# main_board.net
KiCad netlist of a schematic drawn in EAGLE
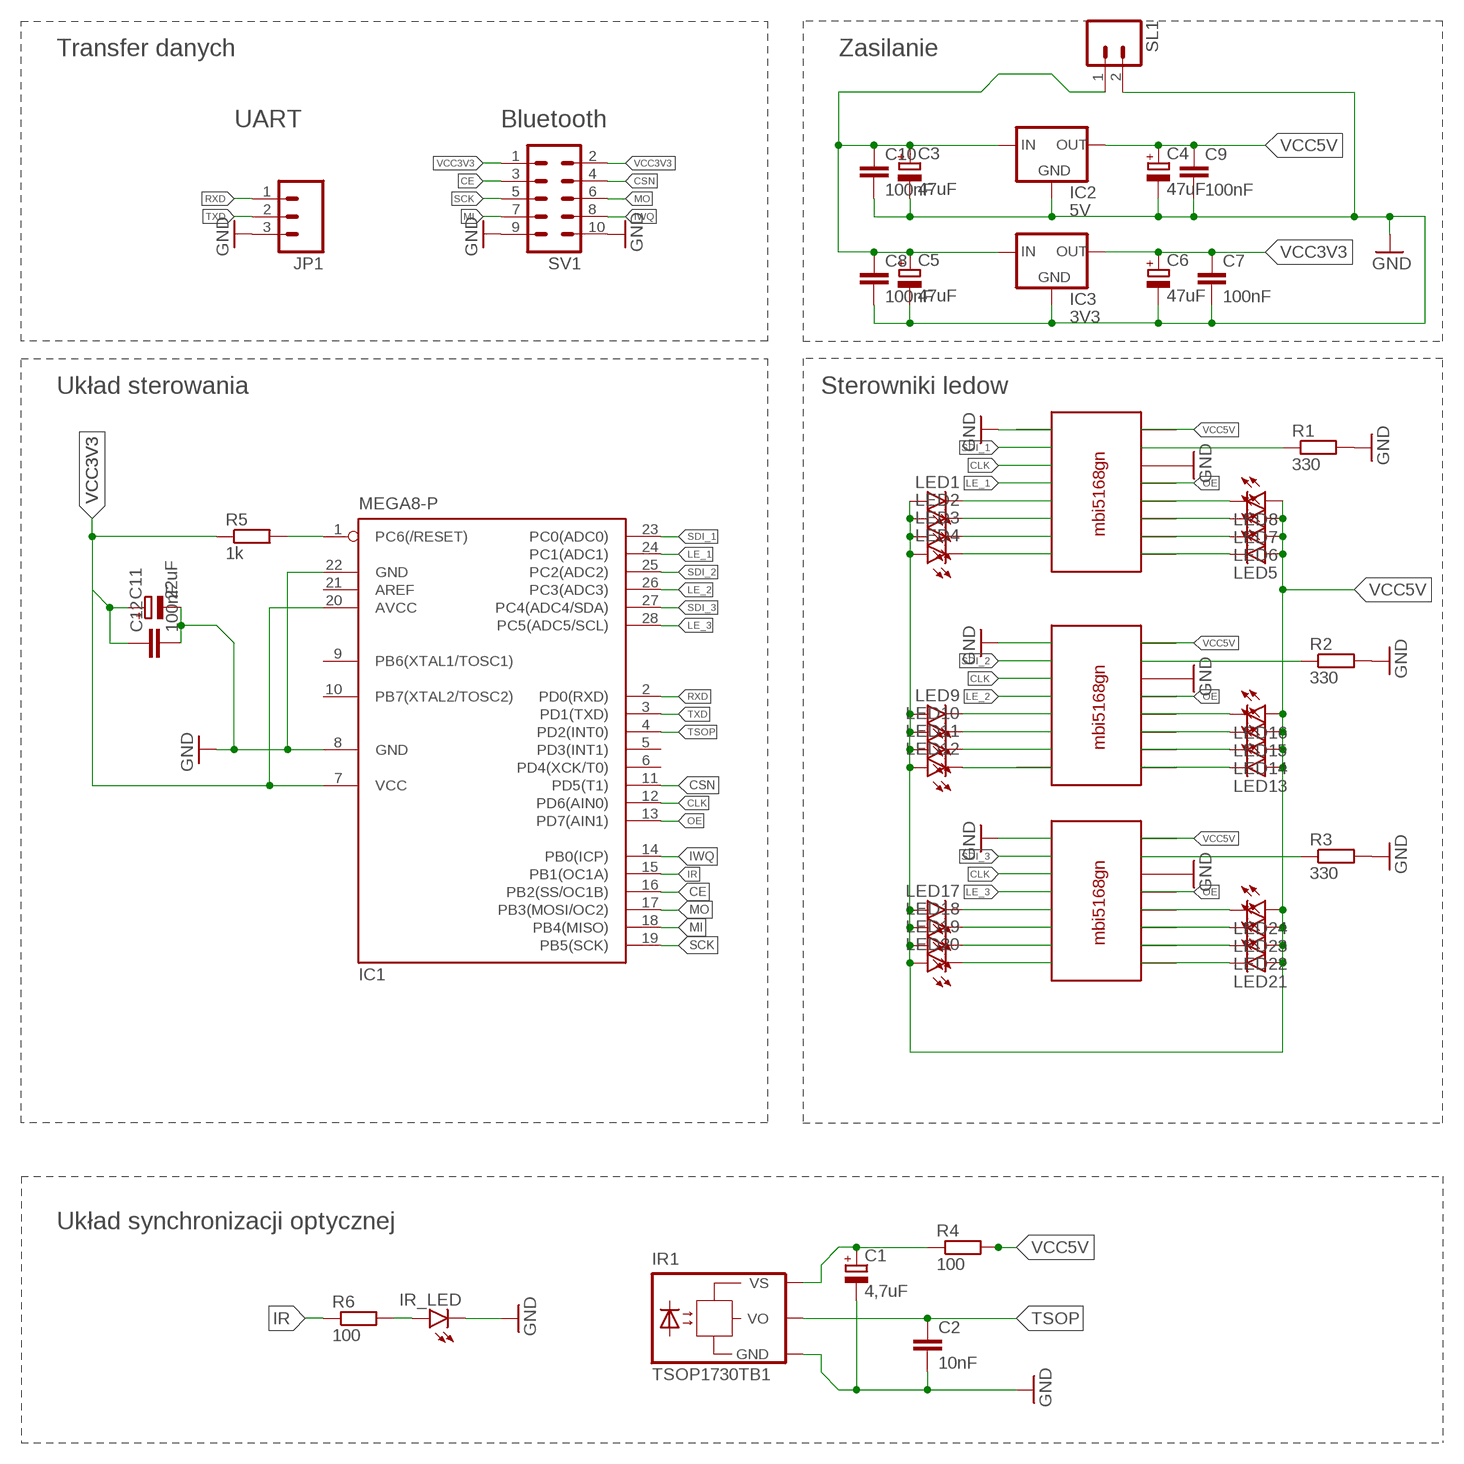
[diagram p0: schematic, sheet 1]

(export (version "E")
  (design (tool "Eeschema 10.0.6"))
  (components
    (comp (ref "C1")
      (value "4,7uF")
      (footprint "eagle-import:B45181A")
      (libsource (lib "eagle-import") (part "CPOL-EUB45181A"))
    )
    (comp (ref "C2")
      (value "10nF")
      (footprint "eagle-import:C025-040X050")
      (libsource (lib "eagle-import") (part "C-EU025-040X050"))
    )
    (comp (ref "C3")
      (value "47uF")
      (footprint "eagle-import:B45181A")
      (libsource (lib "eagle-import") (part "CPOL-EUB45181A"))
    )
    (comp (ref "C4")
      (value "47uF")
      (footprint "eagle-import:B45181A")
      (libsource (lib "eagle-import") (part "CPOL-EUB45181A"))
    )
    (comp (ref "C5")
      (value "47uF")
      (footprint "eagle-import:B45181A")
      (libsource (lib "eagle-import") (part "CPOL-EUB45181A"))
    )
    (comp (ref "C6")
      (value "47uF")
      (footprint "eagle-import:B45181A")
      (libsource (lib "eagle-import") (part "CPOL-EUB45181A"))
    )
    (comp (ref "C7")
      (value "100nF")
      (footprint "eagle-import:C0805")
      (libsource (lib "eagle-import") (part "C-EUC0805"))
    )
    (comp (ref "C8")
      (value "100nF")
      (footprint "eagle-import:C0805")
      (libsource (lib "eagle-import") (part "C-EUC0805"))
    )
    (comp (ref "C9")
      (value "100nF")
      (footprint "eagle-import:C0805")
      (libsource (lib "eagle-import") (part "C-EUC0805"))
    )
    (comp (ref "C10")
      (value "100nF")
      (footprint "eagle-import:C0805")
      (libsource (lib "eagle-import") (part "C-EUC0805"))
    )
    (comp (ref "C11")
      (value "22uF")
      (footprint "eagle-import:B45181A")
      (libsource (lib "eagle-import") (part "CPOL-EUB45181A"))
    )
    (comp (ref "C12")
      (value "100nF")
      (footprint "eagle-import:C025-040X050")
      (libsource (lib "eagle-import") (part "C-EU025-040X050"))
    )
    (comp (ref "IC1")
      (value "MEGA8-P")
      (footprint "eagle-import:DIL28-3")
      (libsource (lib "eagle-import") (part "MEGA8-P"))
    )
    (comp (ref "IC2")
      (value "5V")
      (footprint "eagle-import:TO-220-ALT")
      (libsource (lib "eagle-import") (part "V_REG_78XX-TO-220"))
    )
    (comp (ref "IC3")
      (value "3V3")
      (footprint "eagle-import:TO-220-ALT")
      (libsource (lib "eagle-import") (part "V_REG_78XX-TO-220"))
    )
    (comp (ref "IR1")
      (value "TSOP1730TB1")
      (footprint "eagle-import:TSOP17_TB1")
      (libsource (lib "eagle-import") (part "TSOP17TB130"))
    )
    (comp (ref "IR_LED")
      (value "LED5MM")
      (footprint "eagle-import:LED5MM")
      (libsource (lib "eagle-import") (part "LED5MM"))
    )
    (comp (ref "JP1")
      (value "M03PTH")
      (footprint "eagle-import:1X03")
      (libsource (lib "eagle-import") (part "M03PTH"))
    )
    (comp (ref "LED1")
      (value "LED3MM")
      (footprint "eagle-import:LED3MM")
      (libsource (lib "eagle-import") (part "LED3MM"))
    )
    (comp (ref "LED2")
      (value "LED3MM")
      (footprint "eagle-import:LED3MM")
      (libsource (lib "eagle-import") (part "LED3MM"))
    )
    (comp (ref "LED3")
      (value "LED3MM")
      (footprint "eagle-import:LED3MM")
      (libsource (lib "eagle-import") (part "LED3MM"))
    )
    (comp (ref "LED4")
      (value "LED3MM")
      (footprint "eagle-import:LED3MM")
      (libsource (lib "eagle-import") (part "LED3MM"))
    )
    (comp (ref "LED5")
      (value "LED3MM")
      (footprint "eagle-import:LED3MM")
      (libsource (lib "eagle-import") (part "LED3MM"))
    )
    (comp (ref "LED6")
      (value "LED3MM")
      (footprint "eagle-import:LED3MM")
      (libsource (lib "eagle-import") (part "LED3MM"))
    )
    (comp (ref "LED7")
      (value "LED3MM")
      (footprint "eagle-import:LED3MM")
      (libsource (lib "eagle-import") (part "LED3MM"))
    )
    (comp (ref "LED8")
      (value "LED3MM")
      (footprint "eagle-import:LED3MM")
      (libsource (lib "eagle-import") (part "LED3MM"))
    )
    (comp (ref "LED9")
      (value "LED3MM")
      (footprint "eagle-import:LED3MM")
      (libsource (lib "eagle-import") (part "LED3MM"))
    )
    (comp (ref "LED10")
      (value "LED3MM")
      (footprint "eagle-import:LED3MM")
      (libsource (lib "eagle-import") (part "LED3MM"))
    )
    (comp (ref "LED11")
      (value "LED3MM")
      (footprint "eagle-import:LED3MM")
      (libsource (lib "eagle-import") (part "LED3MM"))
    )
    (comp (ref "LED12")
      (value "LED3MM")
      (footprint "eagle-import:LED3MM")
      (libsource (lib "eagle-import") (part "LED3MM"))
    )
    (comp (ref "LED13")
      (value "LED3MM")
      (footprint "eagle-import:LED3MM")
      (libsource (lib "eagle-import") (part "LED3MM"))
    )
    (comp (ref "LED14")
      (value "LED3MM")
      (footprint "eagle-import:LED3MM")
      (libsource (lib "eagle-import") (part "LED3MM"))
    )
    (comp (ref "LED15")
      (value "LED3MM")
      (footprint "eagle-import:LED3MM")
      (libsource (lib "eagle-import") (part "LED3MM"))
    )
    (comp (ref "LED16")
      (value "LED3MM")
      (footprint "eagle-import:LED3MM")
      (libsource (lib "eagle-import") (part "LED3MM"))
    )
    (comp (ref "LED17")
      (value "LED3MM")
      (footprint "eagle-import:LED3MM")
      (libsource (lib "eagle-import") (part "LED3MM"))
    )
    (comp (ref "LED18")
      (value "LED3MM")
      (footprint "eagle-import:LED3MM")
      (libsource (lib "eagle-import") (part "LED3MM"))
    )
    (comp (ref "LED19")
      (value "LED3MM")
      (footprint "eagle-import:LED3MM")
      (libsource (lib "eagle-import") (part "LED3MM"))
    )
    (comp (ref "LED20")
      (value "LED3MM")
      (footprint "eagle-import:LED3MM")
      (libsource (lib "eagle-import") (part "LED3MM"))
    )
    (comp (ref "LED21")
      (value "LED3MM")
      (footprint "eagle-import:LED3MM")
      (libsource (lib "eagle-import") (part "LED3MM"))
    )
    (comp (ref "LED22")
      (value "LED3MM")
      (footprint "eagle-import:LED3MM")
      (libsource (lib "eagle-import") (part "LED3MM"))
    )
    (comp (ref "LED23")
      (value "LED3MM")
      (footprint "eagle-import:LED3MM")
      (libsource (lib "eagle-import") (part "LED3MM"))
    )
    (comp (ref "LED24")
      (value "LED3MM")
      (footprint "eagle-import:LED3MM")
      (libsource (lib "eagle-import") (part "LED3MM"))
    )
    (comp (ref "R1")
      (value "330")
      (footprint "eagle-import:M0805")
      (libsource (lib "eagle-import") (part "R-EU_M0805"))
    )
    (comp (ref "R2")
      (value "330")
      (footprint "eagle-import:M0805")
      (libsource (lib "eagle-import") (part "R-EU_M0805"))
    )
    (comp (ref "R3")
      (value "330")
      (footprint "eagle-import:M0805")
      (libsource (lib "eagle-import") (part "R-EU_M0805"))
    )
    (comp (ref "R4")
      (value "100")
      (footprint "eagle-import:M0805")
      (libsource (lib "eagle-import") (part "R-EU_M0805"))
    )
    (comp (ref "R5")
      (value "1k")
      (footprint "eagle-import:M0805")
      (libsource (lib "eagle-import") (part "R-EU_M0805"))
    )
    (comp (ref "R6")
      (value "100")
      (footprint "eagle-import:M0805")
      (libsource (lib "eagle-import") (part "R-EU_M0805"))
    )
    (comp (ref "SL1")
      (value "M02")
      (footprint "eagle-import:02P")
      (libsource (lib "eagle-import") (part "M02"))
    )
    (comp (ref "SV1")
      (value "MA05-2")
      (footprint "eagle-import:MA05-2")
      (libsource (lib "eagle-import") (part "MA05-2"))
    )
    (comp (ref "U$1")
      (value "MBI5168GN")
      (footprint "eagle-import:DIL16")
      (libsource (lib "eagle-import") (part "MBI5168GN"))
    )
    (comp (ref "U$2")
      (value "MBI5168GN")
      (footprint "eagle-import:DIL16")
      (libsource (lib "eagle-import") (part "MBI5168GN"))
    )
    (comp (ref "U$3")
      (value "MBI5168GN")
      (footprint "eagle-import:DIL16")
      (libsource (lib "eagle-import") (part "MBI5168GN"))
    )
  )
  (nets
    (net (code "1") (name "CE") (class "Default")
      (node (ref "IC1") (pin "16") (pinfunction "PB2(SS/OC1B)_16") (pintype "bidirectional"))
      (node (ref "SV1") (pin "3") (pinfunction "3_3") (pintype "passive"))
    )
    (net (code "2") (name "CLK") (class "Default")
      (node (ref "IC1") (pin "12") (pinfunction "PD6(AIN0)_12") (pintype "bidirectional"))
      (node (ref "U$1") (pin "CLK") (pinfunction "CLK_CLK") (pintype "output"))
      (node (ref "U$2") (pin "CLK") (pinfunction "CLK_CLK") (pintype "output"))
      (node (ref "U$3") (pin "CLK") (pinfunction "CLK_CLK") (pintype "output"))
    )
    (net (code "3") (name "CSN") (class "Default")
      (node (ref "IC1") (pin "11") (pinfunction "PD5(T1)_11") (pintype "bidirectional"))
      (node (ref "SV1") (pin "4") (pinfunction "4_4") (pintype "passive"))
    )
    (net (code "4") (name "GND") (class "Default")
      (node (ref "C1") (pin "-") (pinfunction "-_-") (pintype "passive"))
      (node (ref "C10") (pin "2") (pinfunction "2_2") (pintype "passive"))
      (node (ref "C11") (pin "-") (pinfunction "-_-") (pintype "passive"))
      (node (ref "C12") (pin "2") (pinfunction "2_2") (pintype "passive"))
      (node (ref "C2") (pin "2") (pinfunction "2_2") (pintype "passive"))
      (node (ref "C3") (pin "-") (pinfunction "-_-") (pintype "passive"))
      (node (ref "C4") (pin "-") (pinfunction "-_-") (pintype "passive"))
      (node (ref "C5") (pin "-") (pinfunction "-_-") (pintype "passive"))
      (node (ref "C6") (pin "-") (pinfunction "-_-") (pintype "passive"))
      (node (ref "C7") (pin "2") (pinfunction "2_2") (pintype "passive"))
      (node (ref "C8") (pin "2") (pinfunction "2_2") (pintype "passive"))
      (node (ref "C9") (pin "2") (pinfunction "2_2") (pintype "passive"))
      (node (ref "IC1") (pin "22") (pinfunction "GND_22") (pintype "power_in"))
      (node (ref "IC1") (pin "8") (pinfunction "GND_8") (pintype "power_in"))
      (node (ref "IC2") (pin "GND") (pinfunction "GND_GND") (pintype "input"))
      (node (ref "IC3") (pin "GND") (pinfunction "GND_GND") (pintype "input"))
      (node (ref "IR1") (pin "GND") (pinfunction "GND_GND") (pintype "power_in"))
      (node (ref "IR_LED") (pin "K") (pinfunction "C_K") (pintype "passive"))
      (node (ref "JP1") (pin "3") (pinfunction "3_3") (pintype "passive"))
      (node (ref "R1") (pin "2") (pinfunction "2_2") (pintype "passive"))
      (node (ref "R2") (pin "2") (pinfunction "2_2") (pintype "passive"))
      (node (ref "R3") (pin "2") (pinfunction "2_2") (pintype "passive"))
      (node (ref "SL1") (pin "2") (pinfunction "2_2") (pintype "passive"))
      (node (ref "SV1") (pin "10") (pinfunction "10_10") (pintype "passive"))
      (node (ref "SV1") (pin "9") (pinfunction "9_9") (pintype "passive"))
      (node (ref "U$1") (pin "GND") (pinfunction "GND_GND") (pintype "output"))
      (node (ref "U$2") (pin "GND") (pinfunction "GND_GND") (pintype "output"))
      (node (ref "U$3") (pin "GND") (pinfunction "GND_GND") (pintype "output"))
    )
    (net (code "5") (name "IR") (class "Default")
      (node (ref "IC1") (pin "15") (pinfunction "PB1(OC1A)_15") (pintype "bidirectional"))
      (node (ref "R6") (pin "1") (pinfunction "1_1") (pintype "passive"))
    )
    (net (code "6") (name "IWQ") (class "Default")
      (node (ref "IC1") (pin "14") (pinfunction "PB0(ICP)_14") (pintype "bidirectional"))
      (node (ref "SV1") (pin "8") (pinfunction "8_8") (pintype "passive"))
    )
    (net (code "7") (name "LE_1") (class "Default")
      (node (ref "IC1") (pin "24") (pinfunction "PC1(ADC1)_24") (pintype "bidirectional"))
      (node (ref "U$1") (pin "LE") (pinfunction "LE_LE") (pintype "output"))
    )
    (net (code "8") (name "LE_2") (class "Default")
      (node (ref "IC1") (pin "26") (pinfunction "PC3(ADC3)_26") (pintype "bidirectional"))
      (node (ref "U$2") (pin "LE") (pinfunction "LE_LE") (pintype "output"))
    )
    (net (code "9") (name "LE_3") (class "Default")
      (node (ref "IC1") (pin "28") (pinfunction "PC5(ADC5/SCL)_28") (pintype "bidirectional"))
      (node (ref "U$3") (pin "LE") (pinfunction "LE_LE") (pintype "output"))
    )
    (net (code "10") (name "MI") (class "Default")
      (node (ref "IC1") (pin "18") (pinfunction "PB4(MISO)_18") (pintype "bidirectional"))
      (node (ref "SV1") (pin "7") (pinfunction "7_7") (pintype "passive"))
    )
    (net (code "11") (name "MO") (class "Default")
      (node (ref "IC1") (pin "17") (pinfunction "PB3(MOSI/OC2)_17") (pintype "bidirectional"))
      (node (ref "SV1") (pin "6") (pinfunction "6_6") (pintype "passive"))
    )
    (net (code "12") (name "Net-(C1-Pad+)") (class "Default")
      (node (ref "C1") (pin "+") (pinfunction "+_+") (pintype "passive"))
      (node (ref "IR1") (pin "VS") (pinfunction "VS_VS") (pintype "power_in"))
      (node (ref "R4") (pin "1") (pinfunction "1_1") (pintype "passive"))
    )
    (net (code "13") (name "Net-(C10-Pad1)") (class "Default")
      (node (ref "C10") (pin "1") (pinfunction "1_1") (pintype "passive"))
      (node (ref "C3") (pin "+") (pinfunction "+_+") (pintype "passive"))
      (node (ref "C5") (pin "+") (pinfunction "+_+") (pintype "passive"))
      (node (ref "C8") (pin "1") (pinfunction "1_1") (pintype "passive"))
      (node (ref "IC2") (pin "IN") (pinfunction "IN_IN") (pintype "input"))
      (node (ref "IC3") (pin "IN") (pinfunction "IN_IN") (pintype "input"))
      (node (ref "SL1") (pin "1") (pinfunction "1_1") (pintype "passive"))
    )
    (net (code "14") (name "Net-(IC1-PC6({slash}RESET))") (class "Default")
      (node (ref "IC1") (pin "1") (pinfunction "PC6(/RESET)_1") (pintype "bidirectional"))
      (node (ref "R5") (pin "2") (pinfunction "2_2") (pintype "passive"))
    )
    (net (code "15") (name "Net-(IR_LED-PadA)") (class "Default")
      (node (ref "IR_LED") (pin "A") (pinfunction "A_A") (pintype "passive"))
      (node (ref "R6") (pin "2") (pinfunction "2_2") (pintype "passive"))
    )
    (net (code "16") (name "Net-(LED1-C)") (class "Default")
      (node (ref "LED1") (pin "K") (pinfunction "C_K") (pintype "passive"))
      (node (ref "U$1") (pin "OUT0") (pinfunction "OUT0_OUT0") (pintype "output"))
    )
    (net (code "17") (name "Net-(LED2-C)") (class "Default")
      (node (ref "LED2") (pin "K") (pinfunction "C_K") (pintype "passive"))
      (node (ref "U$1") (pin "OUT1") (pinfunction "OUT1_OUT1") (pintype "output"))
    )
    (net (code "18") (name "Net-(LED3-C)") (class "Default")
      (node (ref "LED3") (pin "K") (pinfunction "C_K") (pintype "passive"))
      (node (ref "U$1") (pin "OUT2") (pinfunction "OUT2_OUT2") (pintype "output"))
    )
    (net (code "19") (name "Net-(LED4-C)") (class "Default")
      (node (ref "LED4") (pin "K") (pinfunction "C_K") (pintype "passive"))
      (node (ref "U$1") (pin "OUT3") (pinfunction "OUT3_OUT3") (pintype "output"))
    )
    (net (code "20") (name "Net-(LED5-C)") (class "Default")
      (node (ref "LED5") (pin "K") (pinfunction "C_K") (pintype "passive"))
      (node (ref "U$1") (pin "OUT4") (pinfunction "OUT4_OUT4") (pintype "output"))
    )
    (net (code "21") (name "Net-(LED6-C)") (class "Default")
      (node (ref "LED6") (pin "K") (pinfunction "C_K") (pintype "passive"))
      (node (ref "U$1") (pin "OUT5") (pinfunction "OUT5_OUT5") (pintype "output"))
    )
    (net (code "22") (name "Net-(LED7-C)") (class "Default")
      (node (ref "LED7") (pin "K") (pinfunction "C_K") (pintype "passive"))
      (node (ref "U$1") (pin "OUT6") (pinfunction "OUT6_OUT6") (pintype "output"))
    )
    (net (code "23") (name "Net-(LED8-C)") (class "Default")
      (node (ref "LED8") (pin "K") (pinfunction "C_K") (pintype "passive"))
      (node (ref "U$1") (pin "OUT7") (pinfunction "OUT7_OUT7") (pintype "output"))
    )
    (net (code "24") (name "Net-(LED9-C)") (class "Default")
      (node (ref "LED9") (pin "K") (pinfunction "C_K") (pintype "passive"))
      (node (ref "U$2") (pin "OUT0") (pinfunction "OUT0_OUT0") (pintype "output"))
    )
    (net (code "25") (name "Net-(LED10-C)") (class "Default")
      (node (ref "LED10") (pin "K") (pinfunction "C_K") (pintype "passive"))
      (node (ref "U$2") (pin "OUT1") (pinfunction "OUT1_OUT1") (pintype "output"))
    )
    (net (code "26") (name "Net-(LED11-C)") (class "Default")
      (node (ref "LED11") (pin "K") (pinfunction "C_K") (pintype "passive"))
      (node (ref "U$2") (pin "OUT2") (pinfunction "OUT2_OUT2") (pintype "output"))
    )
    (net (code "27") (name "Net-(LED12-C)") (class "Default")
      (node (ref "LED12") (pin "K") (pinfunction "C_K") (pintype "passive"))
      (node (ref "U$2") (pin "OUT3") (pinfunction "OUT3_OUT3") (pintype "output"))
    )
    (net (code "28") (name "Net-(LED13-C)") (class "Default")
      (node (ref "LED13") (pin "K") (pinfunction "C_K") (pintype "passive"))
      (node (ref "U$2") (pin "OUT4") (pinfunction "OUT4_OUT4") (pintype "output"))
    )
    (net (code "29") (name "Net-(LED14-C)") (class "Default")
      (node (ref "LED14") (pin "K") (pinfunction "C_K") (pintype "passive"))
      (node (ref "U$2") (pin "OUT5") (pinfunction "OUT5_OUT5") (pintype "output"))
    )
    (net (code "30") (name "Net-(LED15-C)") (class "Default")
      (node (ref "LED15") (pin "K") (pinfunction "C_K") (pintype "passive"))
      (node (ref "U$2") (pin "OUT6") (pinfunction "OUT6_OUT6") (pintype "output"))
    )
    (net (code "31") (name "Net-(LED16-C)") (class "Default")
      (node (ref "LED16") (pin "K") (pinfunction "C_K") (pintype "passive"))
      (node (ref "U$2") (pin "OUT7") (pinfunction "OUT7_OUT7") (pintype "output"))
    )
    (net (code "32") (name "Net-(LED17-C)") (class "Default")
      (node (ref "LED17") (pin "K") (pinfunction "C_K") (pintype "passive"))
      (node (ref "U$3") (pin "OUT0") (pinfunction "OUT0_OUT0") (pintype "output"))
    )
    (net (code "33") (name "Net-(LED18-C)") (class "Default")
      (node (ref "LED18") (pin "K") (pinfunction "C_K") (pintype "passive"))
      (node (ref "U$3") (pin "OUT1") (pinfunction "OUT1_OUT1") (pintype "output"))
    )
    (net (code "34") (name "Net-(LED19-C)") (class "Default")
      (node (ref "LED19") (pin "K") (pinfunction "C_K") (pintype "passive"))
      (node (ref "U$3") (pin "OUT2") (pinfunction "OUT2_OUT2") (pintype "output"))
    )
    (net (code "35") (name "Net-(LED20-C)") (class "Default")
      (node (ref "LED20") (pin "K") (pinfunction "C_K") (pintype "passive"))
      (node (ref "U$3") (pin "OUT3") (pinfunction "OUT3_OUT3") (pintype "output"))
    )
    (net (code "36") (name "Net-(LED21-C)") (class "Default")
      (node (ref "LED21") (pin "K") (pinfunction "C_K") (pintype "passive"))
      (node (ref "U$3") (pin "OUT4") (pinfunction "OUT4_OUT4") (pintype "output"))
    )
    (net (code "37") (name "Net-(LED22-C)") (class "Default")
      (node (ref "LED22") (pin "K") (pinfunction "C_K") (pintype "passive"))
      (node (ref "U$3") (pin "OUT5") (pinfunction "OUT5_OUT5") (pintype "output"))
    )
    (net (code "38") (name "Net-(LED23-C)") (class "Default")
      (node (ref "LED23") (pin "K") (pinfunction "C_K") (pintype "passive"))
      (node (ref "U$3") (pin "OUT6") (pinfunction "OUT6_OUT6") (pintype "output"))
    )
    (net (code "39") (name "Net-(LED24-C)") (class "Default")
      (node (ref "LED24") (pin "K") (pinfunction "C_K") (pintype "passive"))
      (node (ref "U$3") (pin "OUT7") (pinfunction "OUT7_OUT7") (pintype "output"))
    )
    (net (code "40") (name "Net-(R1-Pad1)") (class "Default")
      (node (ref "R1") (pin "1") (pinfunction "1_1") (pintype "passive"))
      (node (ref "U$1") (pin "R-EXT") (pinfunction "R-EXT_R-EXT") (pintype "output"))
    )
    (net (code "41") (name "Net-(R2-Pad1)") (class "Default")
      (node (ref "R2") (pin "1") (pinfunction "1_1") (pintype "passive"))
      (node (ref "U$2") (pin "R-EXT") (pinfunction "R-EXT_R-EXT") (pintype "output"))
    )
    (net (code "42") (name "Net-(R3-Pad1)") (class "Default")
      (node (ref "R3") (pin "1") (pinfunction "1_1") (pintype "passive"))
      (node (ref "U$3") (pin "R-EXT") (pinfunction "R-EXT_R-EXT") (pintype "output"))
    )
    (net (code "43") (name "OE") (class "Default")
      (node (ref "IC1") (pin "13") (pinfunction "PD7(AIN1)_13") (pintype "bidirectional"))
      (node (ref "U$1") (pin "OE") (pinfunction "OE_OE") (pintype "output"))
      (node (ref "U$2") (pin "OE") (pinfunction "OE_OE") (pintype "output"))
      (node (ref "U$3") (pin "OE") (pinfunction "OE_OE") (pintype "output"))
    )
    (net (code "44") (name "RXD") (class "Default")
      (node (ref "IC1") (pin "2") (pinfunction "PD0(RXD)_2") (pintype "bidirectional"))
      (node (ref "JP1") (pin "1") (pinfunction "1_1") (pintype "passive"))
    )
    (net (code "45") (name "SCK") (class "Default")
      (node (ref "IC1") (pin "19") (pinfunction "PB5(SCK)_19") (pintype "bidirectional"))
      (node (ref "SV1") (pin "5") (pinfunction "5_5") (pintype "passive"))
    )
    (net (code "46") (name "SDI_1") (class "Default")
      (node (ref "IC1") (pin "23") (pinfunction "PC0(ADC0)_23") (pintype "bidirectional"))
      (node (ref "U$1") (pin "SDI") (pinfunction "SDI_SDI") (pintype "output"))
    )
    (net (code "47") (name "SDI_2") (class "Default")
      (node (ref "IC1") (pin "25") (pinfunction "PC2(ADC2)_25") (pintype "bidirectional"))
      (node (ref "U$2") (pin "SDI") (pinfunction "SDI_SDI") (pintype "output"))
    )
    (net (code "48") (name "SDI_3") (class "Default")
      (node (ref "IC1") (pin "27") (pinfunction "PC4(ADC4/SDA)_27") (pintype "bidirectional"))
      (node (ref "U$3") (pin "SDI") (pinfunction "SDI_SDI") (pintype "output"))
    )
    (net (code "49") (name "TSOP") (class "Default")
      (node (ref "C2") (pin "1") (pinfunction "1_1") (pintype "passive"))
      (node (ref "IC1") (pin "4") (pinfunction "PD2(INT0)_4") (pintype "bidirectional"))
      (node (ref "IR1") (pin "VO") (pinfunction "VO_VO") (pintype "open_collector"))
    )
    (net (code "50") (name "TXD") (class "Default")
      (node (ref "IC1") (pin "3") (pinfunction "PD1(TXD)_3") (pintype "bidirectional"))
      (node (ref "JP1") (pin "2") (pinfunction "2_2") (pintype "passive"))
    )
    (net (code "51") (name "VCC3V3") (class "Default")
      (node (ref "C11") (pin "+") (pinfunction "+_+") (pintype "passive"))
      (node (ref "C12") (pin "1") (pinfunction "1_1") (pintype "passive"))
      (node (ref "C6") (pin "+") (pinfunction "+_+") (pintype "passive"))
      (node (ref "C7") (pin "1") (pinfunction "1_1") (pintype "passive"))
      (node (ref "IC1") (pin "20") (pinfunction "AVCC_20") (pintype "power_in"))
      (node (ref "IC1") (pin "7") (pinfunction "VCC_7") (pintype "power_in"))
      (node (ref "IC3") (pin "OUT") (pinfunction "OUT_OUT") (pintype "output"))
      (node (ref "R5") (pin "1") (pinfunction "1_1") (pintype "passive"))
      (node (ref "SV1") (pin "1") (pinfunction "1_1") (pintype "passive"))
      (node (ref "SV1") (pin "2") (pinfunction "2_2") (pintype "passive"))
    )
    (net (code "52") (name "VCC5V") (class "Default")
      (node (ref "C4") (pin "+") (pinfunction "+_+") (pintype "passive"))
      (node (ref "C9") (pin "1") (pinfunction "1_1") (pintype "passive"))
      (node (ref "IC2") (pin "OUT") (pinfunction "OUT_OUT") (pintype "output"))
      (node (ref "LED1") (pin "A") (pinfunction "A_A") (pintype "passive"))
      (node (ref "LED10") (pin "A") (pinfunction "A_A") (pintype "passive"))
      (node (ref "LED11") (pin "A") (pinfunction "A_A") (pintype "passive"))
      (node (ref "LED12") (pin "A") (pinfunction "A_A") (pintype "passive"))
      (node (ref "LED13") (pin "A") (pinfunction "A_A") (pintype "passive"))
      (node (ref "LED14") (pin "A") (pinfunction "A_A") (pintype "passive"))
      (node (ref "LED15") (pin "A") (pinfunction "A_A") (pintype "passive"))
      (node (ref "LED16") (pin "A") (pinfunction "A_A") (pintype "passive"))
      (node (ref "LED17") (pin "A") (pinfunction "A_A") (pintype "passive"))
      (node (ref "LED18") (pin "A") (pinfunction "A_A") (pintype "passive"))
      (node (ref "LED19") (pin "A") (pinfunction "A_A") (pintype "passive"))
      (node (ref "LED2") (pin "A") (pinfunction "A_A") (pintype "passive"))
      (node (ref "LED20") (pin "A") (pinfunction "A_A") (pintype "passive"))
      (node (ref "LED21") (pin "A") (pinfunction "A_A") (pintype "passive"))
      (node (ref "LED22") (pin "A") (pinfunction "A_A") (pintype "passive"))
      (node (ref "LED23") (pin "A") (pinfunction "A_A") (pintype "passive"))
      (node (ref "LED24") (pin "A") (pinfunction "A_A") (pintype "passive"))
      (node (ref "LED3") (pin "A") (pinfunction "A_A") (pintype "passive"))
      (node (ref "LED4") (pin "A") (pinfunction "A_A") (pintype "passive"))
      (node (ref "LED5") (pin "A") (pinfunction "A_A") (pintype "passive"))
      (node (ref "LED6") (pin "A") (pinfunction "A_A") (pintype "passive"))
      (node (ref "LED7") (pin "A") (pinfunction "A_A") (pintype "passive"))
      (node (ref "LED8") (pin "A") (pinfunction "A_A") (pintype "passive"))
      (node (ref "LED9") (pin "A") (pinfunction "A_A") (pintype "passive"))
      (node (ref "R4") (pin "2") (pinfunction "2_2") (pintype "passive"))
      (node (ref "U$1") (pin "VCC") (pinfunction "VCC_VCC") (pintype "output"))
      (node (ref "U$2") (pin "VCC") (pinfunction "VCC_VCC") (pintype "output"))
      (node (ref "U$3") (pin "VCC") (pinfunction "VCC_VCC") (pintype "output"))
    )
    (net (code "53") (name "unconnected-(IC1-AREF-Pad21)") (class "Default")
      (node (ref "IC1") (pin "21") (pinfunction "AREF_21") (pintype "passive"))
    )
    (net (code "54") (name "unconnected-(IC1-PB6(XTAL1{slash}TOSC1)-Pad9)") (class "Default")
      (node (ref "IC1") (pin "9") (pinfunction "PB6(XTAL1/TOSC1)_9") (pintype "bidirectional"))
    )
    (net (code "55") (name "unconnected-(IC1-PB7(XTAL2{slash}TOSC2)-Pad10)") (class "Default")
      (node (ref "IC1") (pin "10") (pinfunction "PB7(XTAL2/TOSC2)_10") (pintype "bidirectional"))
    )
    (net (code "56") (name "unconnected-(IC1-PD3(INT1)-Pad5)") (class "Default")
      (node (ref "IC1") (pin "5") (pinfunction "PD3(INT1)_5") (pintype "bidirectional"))
    )
    (net (code "57") (name "unconnected-(IC1-PD4(XCK{slash}T0)-Pad6)") (class "Default")
      (node (ref "IC1") (pin "6") (pinfunction "PD4(XCK/T0)_6") (pintype "bidirectional"))
    )
    (net (code "58") (name "unconnected-(U$1-PadSDO)") (class "Default")
      (node (ref "U$1") (pin "SDO") (pinfunction "SDO_SDO") (pintype "output"))
    )
    (net (code "59") (name "unconnected-(U$2-PadSDO)") (class "Default")
      (node (ref "U$2") (pin "SDO") (pinfunction "SDO_SDO") (pintype "output"))
    )
    (net (code "60") (name "unconnected-(U$3-PadSDO)") (class "Default")
      (node (ref "U$3") (pin "SDO") (pinfunction "SDO_SDO") (pintype "output"))
    )
  )
)
